# GPS_POWER.net
KiCad netlist of a schematic drawn in Altium Designer
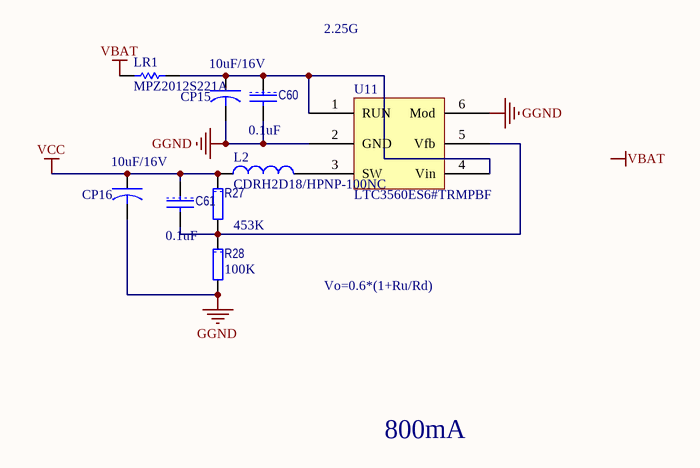
[diagram p0: GPS POWER.SchDoc]

(export (version "E")
  (design (tool "Eeschema 10.0.6"))
  (components
    (comp (ref "C60")
      (value "0.1uF")
      (footprint "1608[0603]C")
      (description "多层陶瓷电容器MLCC - SMD/SMT 0603 0.1uF 50volts X7R 10%")
      (fields (field (name "MANUFACTURER") "TDK") (field (name "MANUFACTURER PART NUMBER") "C1608X7R1H104K"))
      (libsource (lib "*") (part "CAP"))
    )
    (comp (ref "C61")
      (value "0.1uF")
      (footprint "1608[0603]C")
      (description "多层陶瓷电容器MLCC - SMD/SMT 0603 0.1uF 50volts X7R 10%")
      (fields (field (name "MANUFACTURER") "TDK") (field (name "MANUFACTURER PART NUMBER") "C1608X7R1H104K"))
      (libsource (lib "*") (part "CAP"))
    )
    (comp (ref "CP15")
      (value "10uF/16V")
      (footprint "3216[1206]CB")
      (description "钽质电容器-固体SMD 16volts 10uF 10%")
      (fields (field (name "MANUFACTURER") "AVX") (field (name "MANUFACTURER PART NUMBER") "TAJA106K016RNJ"))
      (libsource (lib "*") (part "CAPACITOR"))
    )
    (comp (ref "CP16")
      (value "10uF/16V")
      (footprint "3216[1206]CB")
      (description "钽质电容器-固体SMD 16volts 10uF 10%")
      (fields (field (name "MANUFACTURER") "AVX") (field (name "MANUFACTURER PART NUMBER") "TAJA106K016RNJ"))
      (libsource (lib "*") (part "CAPACITOR"))
    )
    (comp (ref "L2")
      (value "CDRH2D18/HPNP-100NC")
      (footprint "INDP3232")
      (description "固定电感器 10uH 430mA")
      (fields (field (name "MANUFACTURER") "Sumida"))
      (libsource (lib "Miscellaneous Devices") (part "Inductor"))
    )
    (comp (ref "LR1")
      (value "MPZ2012S221A")
      (footprint "2012[0805]")
      (description "电磁干扰滤波珠子、扼流圈和阵列 Ferrite Chip Beads")
      (fields (field (name "MANUFACTURER") "TDK"))
      (libsource (lib "Miscellaneous Devices") (part "Res Semi"))
    )
    (comp (ref "R27")
      (value "453K")
      (footprint "1608[0603]R")
      (description "薄膜电阻器 - SMD 453Kohms .1% 25ppm")
      (fields
        (field (name "MANUFACTURER") "Vishay")
        (field (name "MANUFACTURER PART NUMBER") "TNPW0805453KBEEN")
      )
      (libsource (lib "10K 1%") (part "RES"))
    )
    (comp (ref "R28")
      (value "100K")
      (footprint "1608[0603]R")
      (description "厚膜电阻器 - SMD 1/10watt 100Kohms 1%")
      (fields
        (field (name "MANUFACTURER") "Vishay / Dale")
        (field (name "MANUFACTURER PART NUMBER") "CRCW0603100KFKEA")
      )
      (libsource (lib "100K 1%") (part "RES"))
    )
    (comp (ref "U11")
      (value "LTC3560ES6#TRMPBF")
      (footprint "SOT26A-6N")
      (description "IC REG BUCK SYNC ADJ TSOT23-6")
      (fields (field (name "MANUFACTURER") "Linear Technology"))
      (libsource (lib "S3C2440V9") (part "LTC3405A"))
    )
  )
  (nets
    (net (code "1") (name "GGND") (class "Default")
      (node (ref "C60") (pin "2") (pinfunction "2_2") (pintype "passive"))
      (node (ref "CP15") (pin "2") (pinfunction "2_2") (pintype "passive"))
      (node (ref "CP16") (pin "2") (pinfunction "2_2") (pintype "passive"))
      (node (ref "R28") (pin "2") (pinfunction "2_2") (pintype "passive"))
      (node (ref "U11") (pin "2") (pinfunction "GND_2") (pintype "passive"))
      (node (ref "U11") (pin "6") (pinfunction "Mod_6") (pintype "passive"))
    )
    (net (code "2") (name "Net-(U11-RUN)") (class "Default")
      (node (ref "C60") (pin "1") (pinfunction "1_1") (pintype "passive"))
      (node (ref "CP15") (pin "1") (pinfunction "1_1") (pintype "passive"))
      (node (ref "LR1") (pin "1") (pinfunction "1_1") (pintype "passive"))
      (node (ref "U11") (pin "1") (pinfunction "RUN_1") (pintype "passive"))
      (node (ref "U11") (pin "4") (pinfunction "Vin_4") (pintype "passive"))
    )
    (net (code "3") (name "Net-(U11-SW)") (class "Default")
      (node (ref "L2") (pin "2") (pinfunction "2_2") (pintype "passive"))
      (node (ref "U11") (pin "3") (pinfunction "SW_3") (pintype "passive"))
    )
    (net (code "4") (name "Net-(U11-Vfb)") (class "Default")
      (node (ref "C61") (pin "2") (pinfunction "2_2") (pintype "passive"))
      (node (ref "R27") (pin "2") (pinfunction "2_2") (pintype "passive"))
      (node (ref "R28") (pin "1") (pinfunction "1_1") (pintype "passive"))
      (node (ref "U11") (pin "5") (pinfunction "Vfb_5") (pintype "passive"))
    )
    (net (code "5") (name "VBAT") (class "Default")
      (node (ref "LR1") (pin "2") (pinfunction "2_2") (pintype "passive"))
    )
    (net (code "6") (name "VCC") (class "Default")
      (node (ref "C61") (pin "1") (pinfunction "1_1") (pintype "passive"))
      (node (ref "CP16") (pin "1") (pinfunction "1_1") (pintype "passive"))
      (node (ref "L2") (pin "1") (pinfunction "1_1") (pintype "passive"))
      (node (ref "R27") (pin "1") (pinfunction "1_1") (pintype "passive"))
    )
  )
)
